# MCU_32.net
KiCad netlist of a schematic drawn in Altium Designer
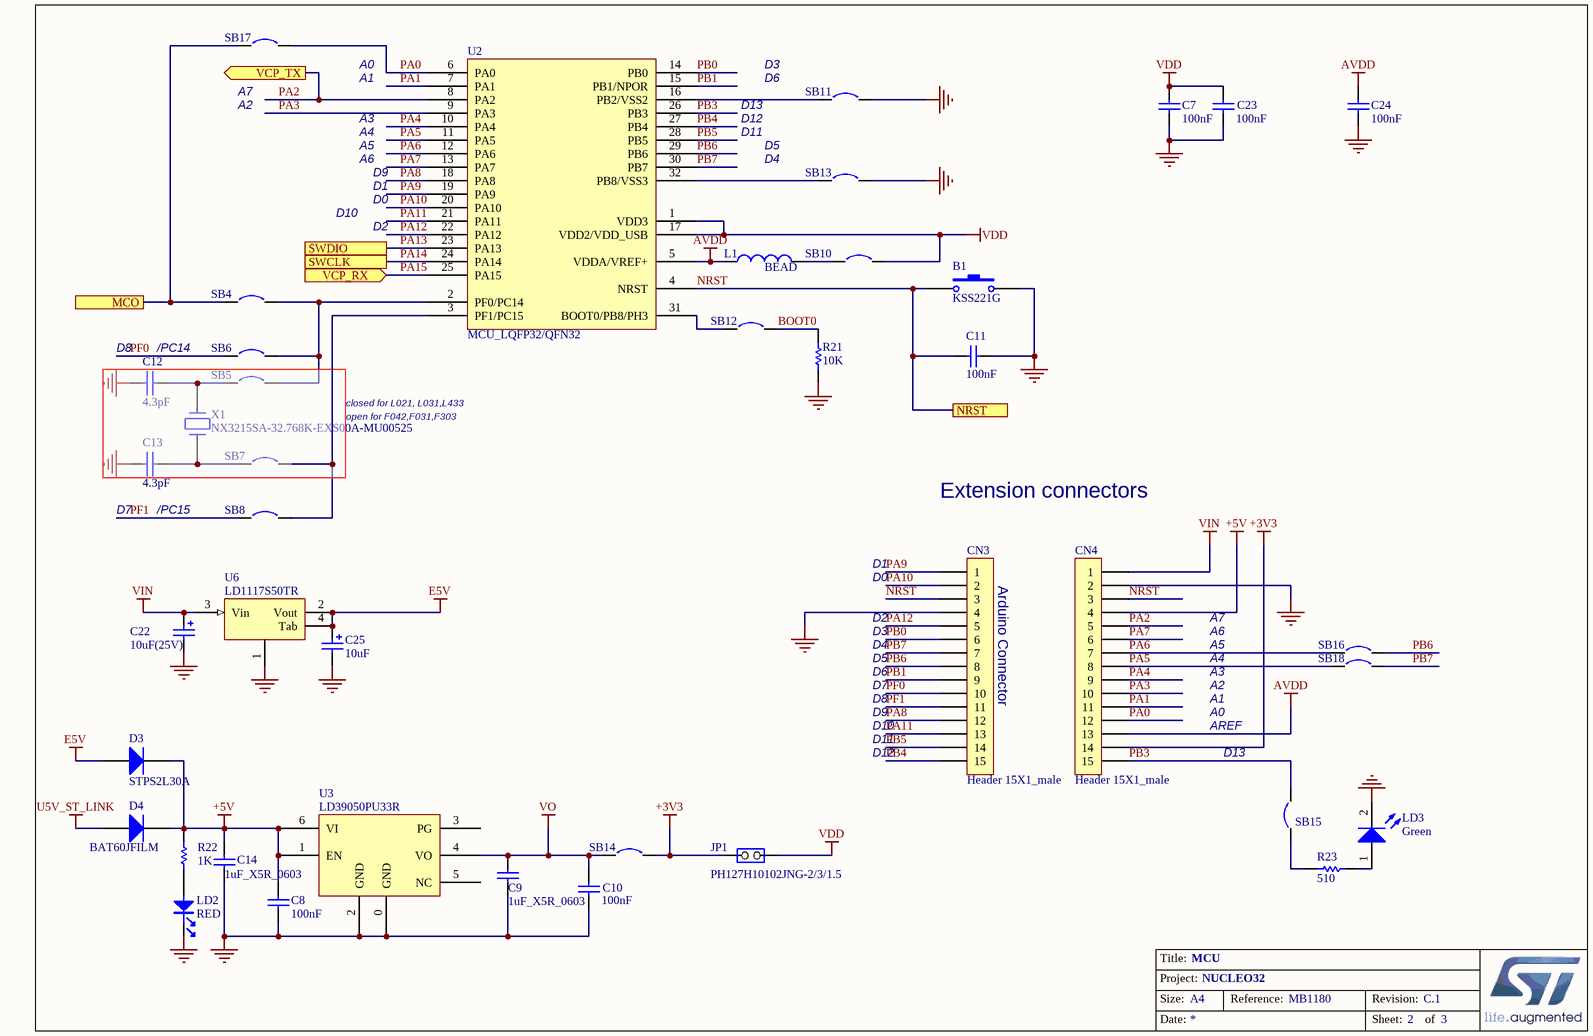
[diagram p0: MCU_32.SchDoc]

(export (version "E")
  (design (tool "Eeschema 10.0.6"))
  (components
    (comp (ref "B1")
      (value "KSS221G")
      (footprint "SW2_5R6_5R5x3R1")
      (description "Switch")
      (fields (field (name "PUBLISHER") "Altium Limited"))
      (libsource (lib "Miscellaneous Devices") (part "SW-PB"))
    )
    (comp (ref "C7")
      (value "100nF")
      (footprint "0603C")
      (description "Capacitor")
      (fields (field (name "PUBLISHER") "Altium Limited"))
      (libsource (lib "Miscellaneous Devices") (part "Cap"))
    )
    (comp (ref "C8")
      (value "100nF")
      (footprint "0603C")
      (description "Capacitor 0402 / 0603 / 0805")
      (libsource (lib "MCD_TOOLS") (part "Capacitor_ST"))
    )
    (comp (ref "C9")
      (value "1uF_X5R_0603")
      (footprint "0603C")
      (description "0603  X5R 1µF")
      (fields (field (name "TOLERANCE") "10%"))
      (libsource (lib "MB963_1") (part "CAP SMD 0603  X5R 1µF 25V 10%"))
    )
    (comp (ref "C10")
      (value "100nF")
      (footprint "0603C")
      (description "Capacitor 0402 / 0603 / 0805")
      (libsource (lib "MCD_TOOLS") (part "Capacitor_ST"))
    )
    (comp (ref "C11")
      (value "100nF")
      (footprint "0603C")
      (description "Capacitor")
      (fields (field (name "PUBLISHER") "Altium Limited"))
      (libsource (lib "Miscellaneous Devices") (part "CAP"))
    )
    (comp (ref "C12")
      (value "4.3pF")
      (footprint "0603C")
      (description "Capacitor")
      (libsource (lib "*") (part "CAP"))
    )
    (comp (ref "C13")
      (value "4.3pF")
      (footprint "0603C")
      (description "Capacitor")
      (libsource (lib "*") (part "CAP"))
    )
    (comp (ref "C14")
      (value "1uF_X5R_0603")
      (footprint "0603C")
      (description "0603  X5R 1µF")
      (fields (field (name "TOLERANCE") "10%"))
      (libsource (lib "MB963_1") (part "CAP SMD 0603  X5R 1µF 25V 10%"))
    )
    (comp (ref "C22")
      (value "10uF(25V)")
      (footprint "TAN_B")
      (description "Polarized Capacitor (Radial)")
      (fields (field (name "PUBLISHER") "Altium Limited"))
      (libsource (lib "Miscellaneous Devices") (part "Cap Pol1"))
    )
    (comp (ref "C23")
      (value "100nF")
      (footprint "0603C")
      (description "Capacitor")
      (fields (field (name "PUBLISHER") "Altium Limited"))
      (libsource (lib "Miscellaneous Devices") (part "Cap"))
    )
    (comp (ref "C24")
      (value "100nF")
      (footprint "0603C")
      (description "Capacitor")
      (fields (field (name "PUBLISHER") "Altium Limited"))
      (libsource (lib "Miscellaneous Devices") (part "Cap"))
    )
    (comp (ref "C25")
      (value "10uF")
      (footprint "TAN_A")
      (description "Polarized Capacitor (Radial)")
      (fields (field (name "PUBLISHER") "Altium Limited"))
      (libsource (lib "Miscellaneous Devices") (part "Cap Pol1"))
    )
    (comp (ref "CN3")
      (value "Header 15X1_male")
      (footprint "HDR_1x15_2R54_V_F")
      (description "Header, 10-Pin, Single row,female")
      (fields (field (name "PUBLISHER") "Altium Limited"))
      (libsource (lib "") (part "Header 15X1_Female_1_1"))
    )
    (comp (ref "CN4")
      (value "Header 15X1_male")
      (footprint "HDR_1x15_2R54_V_F")
      (description "Header, 10-Pin, Single row,female")
      (fields (field (name "PUBLISHER") "Altium Limited"))
      (libsource (lib "MB1180") (part "Header 15X1_Female_1"))
    )
    (comp (ref "D3") (value "STPS2L30A") (footprint "SMA") (libsource (lib "Nucleo_64") (part "STPS2L30A")))
    (comp (ref "D4")
      (value "BAT60JFILM")
      (footprint "SOD-323")
      (libsource (lib "MCD_TOOLS") (part "BAT60JFILM"))
    )
    (comp (ref "JP1")
      (value "PH127H10102JNG-2/3/1.5")
      (footprint "HDR_1x2_1R27_R_M")
      (libsource (lib "*") (part "JP2"))
    )
    (comp (ref "L1")
      (value "BEAD")
      (footprint "0603L")
      (description "Inductor")
      (fields (field (name "PUBLISHER") "Altium Limited"))
      (libsource (lib "Miscellaneous Devices") (part "Inductor"))
    )
    (comp (ref "LD2") (value "RED") (footprint "0603D_R") (libsource (lib "MB963_1") (part "PHOTO")))
    (comp (ref "LD3")
      (value "Green")
      (footprint "0603D_G")
      (description "Typical RED, GREEN, YELLOW, AMBER GaAs LED")
      (fields (field (name "PUBLISHER") "Altium Limited"))
      (libsource (lib "Miscellaneous Devices") (part "LED2"))
    )
    (comp (ref "R21")
      (value "10K")
      (footprint "0603R")
      (description "Resistor")
      (fields (field (name "PUBLISHER") "Altium Limited"))
      (libsource (lib "Miscellaneous Devices") (part "res1"))
    )
    (comp (ref "R22")
      (value "1K")
      (footprint "0603R")
      (description "Resistor 0402 / 0603 / 0805")
      (libsource (lib "MCD_TOOLS") (part "Resistor_ST"))
    )
    (comp (ref "R23")
      (value "510")
      (footprint "0603R")
      (description "Resistor")
      (fields (field (name "PUBLISHER") "Altium Limited"))
      (libsource (lib "Miscellaneous Devices") (part "Res1"))
    )
    (comp (ref "SB4")
      (value "Circuit Breaker (open)")
      (footprint "SB_0603")
      (description "Circuit Breaker")
      (fields (field (name "PUBLISHER") "Altium Limited"))
      (libsource (lib "MCD_TOOLS") (part "Circuit Breaker"))
    )
    (comp (ref "SB5")
      (value "Circuit Breaker")
      (footprint "SB_0603")
      (fields (field (name "PUBLISHER") "Altium Limited"))
      (libsource (lib "MCD_TOOLS") (part "Circuit Breaker"))
    )
    (comp (ref "SB6")
      (value "Circuit Breaker")
      (footprint "SB_0603")
      (fields (field (name "PUBLISHER") "Altium Limited"))
      (libsource (lib "MCD_TOOLS") (part "Circuit Breaker"))
    )
    (comp (ref "SB7")
      (value "Circuit Breaker")
      (footprint "SB_0603")
      (fields (field (name "PUBLISHER") "Altium Limited"))
      (libsource (lib "MCD_TOOLS") (part "Circuit Breaker"))
    )
    (comp (ref "SB8")
      (value "Circuit Breaker")
      (footprint "SB_0603")
      (fields (field (name "PUBLISHER") "Altium Limited"))
      (libsource (lib "MCD_TOOLS") (part "Circuit Breaker"))
    )
    (comp (ref "SB10")
      (value "Circuit Breaker (close)")
      (footprint "SB_0603")
      (description "Circuit Breaker")
      (fields (field (name "PUBLISHER") "Altium Limited"))
      (libsource (lib "MCD_TOOLS") (part "Circuit Breaker"))
    )
    (comp (ref "SB11")
      (value "Circuit Breaker (close)")
      (footprint "SB_0603")
      (description "Circuit Breaker")
      (fields (field (name "PUBLISHER") "Altium Limited"))
      (libsource (lib "MCD_TOOLS") (part "Circuit Breaker"))
    )
    (comp (ref "SB12")
      (value "Circuit Breaker (close)")
      (footprint "SB_0603")
      (description "Circuit Breaker")
      (fields (field (name "PUBLISHER") "Altium Limited"))
      (libsource (lib "MCD_TOOLS") (part "Circuit Breaker"))
    )
    (comp (ref "SB13")
      (value "Circuit Breaker (close)")
      (footprint "SB_0603")
      (description "Circuit Breaker")
      (fields (field (name "PUBLISHER") "Altium Limited"))
      (libsource (lib "MCD_TOOLS") (part "Circuit Breaker"))
    )
    (comp (ref "SB14")
      (value "Circuit Breaker (close)")
      (footprint "SB_0603")
      (description "Circuit Breaker")
      (fields (field (name "PUBLISHER") "Altium Limited"))
      (libsource (lib "MCD_TOOLS") (part "Circuit Breaker"))
    )
    (comp (ref "SB15")
      (value "Circuit Breaker (close)")
      (footprint "SB_0603")
      (description "Circuit Breaker")
      (fields (field (name "PUBLISHER") "Altium Limited"))
      (libsource (lib "MCD_TOOLS") (part "Circuit Breaker"))
    )
    (comp (ref "SB16")
      (value "Circuit Breaker (close)")
      (footprint "SB_0603")
      (description "Circuit Breaker")
      (fields (field (name "PUBLISHER") "Altium Limited"))
      (libsource (lib "MCD_TOOLS") (part "Circuit Breaker"))
    )
    (comp (ref "SB17")
      (value "Circuit Breaker (open)")
      (footprint "SB_0603")
      (description "Circuit Breaker")
      (fields (field (name "PUBLISHER") "Altium Limited"))
      (libsource (lib "MCD_TOOLS") (part "Circuit Breaker"))
    )
    (comp (ref "SB18")
      (value "Circuit Breaker (close)")
      (footprint "SB_0603")
      (description "Circuit Breaker")
      (fields (field (name "PUBLISHER") "Altium Limited"))
      (libsource (lib "MCD_TOOLS") (part "Circuit Breaker"))
    )
    (comp (ref "U2")
      (value "MCU_LQFP32/QFN32")
      (footprint "LQFP32_0R5_7x7")
      (libsource (lib "MB1180") (part "MCU_LQFP32"))
    )
    (comp (ref "U3")
      (value "LD39050PU33R")
      (footprint "DFN6_0R95_3x3_TP")
      (libsource (lib "MB1180") (part "LD39050P"))
    )
    (comp (ref "U6") (value "LD1117S50TR") (footprint "SOT-223") (libsource (lib "MB1180") (part "LD1117")))
    (comp (ref "X1")
      (value "NX3215SA-32.768K-EXS00A-MU00525")
      (footprint "XTAL_2SM_3R2X1R5")
      (description "Crystal")
      (libsource (lib "MB1167") (part "CRYSTAL_32K"))
    )
  )
  (nets
    (net (code "1") (name "+3V3") (class "Default")
      (node (ref "CN4") (pin "14") (pinfunction "14_14") (pintype "passive"))
      (node (ref "JP1") (pin "1") (pinfunction "COMMON_1") (pintype "passive"))
      (node (ref "SB14") (pin "2") (pinfunction "2_2") (pintype "passive"))
    )
    (net (code "2") (name "+5V") (class "Default")
      (node (ref "C14") (pin "1") (pinfunction "1_1") (pintype "passive"))
      (node (ref "C8") (pin "2") (pinfunction "2_2") (pintype "passive"))
      (node (ref "CN4") (pin "4") (pinfunction "4_4") (pintype "passive"))
      (node (ref "D3") (pin "2") (pinfunction "K_2") (pintype "passive"))
      (node (ref "D4") (pin "2") (pinfunction "K_2") (pintype "passive"))
      (node (ref "R22") (pin "2") (pinfunction "2_2") (pintype "passive"))
      (node (ref "U3") (pin "1") (pinfunction "EN_1") (pintype "passive"))
      (node (ref "U3") (pin "6") (pinfunction "VI_6") (pintype "passive"))
    )
    (net (code "3") (name "/BOOT0") (class "Default")
      (node (ref "R21") (pin "1") (pinfunction "1_1") (pintype "passive"))
      (node (ref "SB12") (pin "2") (pinfunction "2_2") (pintype "passive"))
    )
    (net (code "4") (name "/MCO") (class "Default")
      (node (ref "SB17") (pin "1") (pinfunction "1_1") (pintype "passive"))
      (node (ref "SB4") (pin "1") (pinfunction "1_1") (pintype "passive"))
    )
    (net (code "5") (name "/NRST") (class "Default")
      (node (ref "B1") (pin "1") (pinfunction "1_1") (pintype "passive"))
      (node (ref "C11") (pin "2") (pinfunction "2_2") (pintype "passive"))
      (node (ref "CN3") (pin "3") (pinfunction "3_3") (pintype "passive"))
      (node (ref "CN4") (pin "3") (pinfunction "3_3") (pintype "passive"))
      (node (ref "U2") (pin "4") (pinfunction "NRST_4") (pintype "passive"))
    )
    (net (code "6") (name "/PA0") (class "Default")
      (node (ref "CN4") (pin "12") (pinfunction "12_12") (pintype "passive"))
      (node (ref "SB17") (pin "2") (pinfunction "2_2") (pintype "passive"))
      (node (ref "U2") (pin "6") (pinfunction "PA0_6") (pintype "passive"))
    )
    (net (code "7") (name "/PA1") (class "Default")
      (node (ref "CN4") (pin "11") (pinfunction "11_11") (pintype "passive"))
      (node (ref "U2") (pin "7") (pinfunction "PA1_7") (pintype "passive"))
    )
    (net (code "8") (name "/PA2") (class "Default")
      (node (ref "CN4") (pin "5") (pinfunction "5_5") (pintype "passive"))
      (node (ref "U2") (pin "8") (pinfunction "PA2_8") (pintype "passive"))
    )
    (net (code "9") (name "/PA3") (class "Default")
      (node (ref "CN4") (pin "10") (pinfunction "10_10") (pintype "passive"))
      (node (ref "U2") (pin "9") (pinfunction "PA3_9") (pintype "passive"))
    )
    (net (code "10") (name "/PA4") (class "Default")
      (node (ref "CN4") (pin "9") (pinfunction "9_9") (pintype "passive"))
      (node (ref "U2") (pin "10") (pinfunction "PA4_10") (pintype "passive"))
    )
    (net (code "11") (name "/PA5") (class "Default")
      (node (ref "CN4") (pin "8") (pinfunction "8_8") (pintype "passive"))
      (node (ref "SB18") (pin "1") (pinfunction "1_1") (pintype "passive"))
      (node (ref "U2") (pin "11") (pinfunction "PA5_11") (pintype "passive"))
    )
    (net (code "12") (name "/PA6") (class "Default")
      (node (ref "CN4") (pin "7") (pinfunction "7_7") (pintype "passive"))
      (node (ref "SB16") (pin "1") (pinfunction "1_1") (pintype "passive"))
      (node (ref "U2") (pin "12") (pinfunction "PA6_12") (pintype "passive"))
    )
    (net (code "13") (name "/PA7") (class "Default")
      (node (ref "CN4") (pin "6") (pinfunction "6_6") (pintype "passive"))
      (node (ref "U2") (pin "13") (pinfunction "PA7_13") (pintype "passive"))
    )
    (net (code "14") (name "/PA8") (class "Default")
      (node (ref "CN3") (pin "12") (pinfunction "12_12") (pintype "passive"))
      (node (ref "U2") (pin "18") (pinfunction "PA8_18") (pintype "passive"))
    )
    (net (code "15") (name "/PA9") (class "Default")
      (node (ref "CN3") (pin "1") (pinfunction "1_1") (pintype "passive"))
      (node (ref "U2") (pin "19") (pinfunction "PA9_19") (pintype "passive"))
    )
    (net (code "16") (name "/PA10") (class "Default")
      (node (ref "CN3") (pin "2") (pinfunction "2_2") (pintype "passive"))
      (node (ref "U2") (pin "20") (pinfunction "PA10_20") (pintype "passive"))
    )
    (net (code "17") (name "/PA11") (class "Default")
      (node (ref "CN3") (pin "13") (pinfunction "13_13") (pintype "passive"))
      (node (ref "U2") (pin "21") (pinfunction "PA11_21") (pintype "passive"))
    )
    (net (code "18") (name "/PA12") (class "Default")
      (node (ref "CN3") (pin "5") (pinfunction "5_5") (pintype "passive"))
      (node (ref "U2") (pin "22") (pinfunction "PA12_22") (pintype "passive"))
    )
    (net (code "19") (name "/PA13") (class "Default")
      (node (ref "U2") (pin "23") (pinfunction "PA13_23") (pintype "passive"))
    )
    (net (code "20") (name "/PA14") (class "Default")
      (node (ref "U2") (pin "24") (pinfunction "PA14_24") (pintype "passive"))
    )
    (net (code "21") (name "/PA15") (class "Default")
      (node (ref "U2") (pin "25") (pinfunction "PA15_25") (pintype "passive"))
    )
    (net (code "22") (name "/PB0") (class "Default")
      (node (ref "CN3") (pin "6") (pinfunction "6_6") (pintype "passive"))
      (node (ref "U2") (pin "14") (pinfunction "PB0_14") (pintype "passive"))
    )
    (net (code "23") (name "/PB1") (class "Default")
      (node (ref "CN3") (pin "9") (pinfunction "9_9") (pintype "passive"))
      (node (ref "U2") (pin "15") (pinfunction "PB1/NPOR_15") (pintype "passive"))
    )
    (net (code "24") (name "/PB3") (class "Default")
      (node (ref "CN4") (pin "15") (pinfunction "15_15") (pintype "passive"))
      (node (ref "SB15") (pin "2") (pinfunction "2_2") (pintype "passive"))
      (node (ref "U2") (pin "26") (pinfunction "PB3_26") (pintype "passive"))
    )
    (net (code "25") (name "/PB4") (class "Default")
      (node (ref "CN3") (pin "15") (pinfunction "15_15") (pintype "passive"))
      (node (ref "U2") (pin "27") (pinfunction "PB4_27") (pintype "passive"))
    )
    (net (code "26") (name "/PB5") (class "Default")
      (node (ref "CN3") (pin "14") (pinfunction "14_14") (pintype "passive"))
      (node (ref "U2") (pin "28") (pinfunction "PB5_28") (pintype "passive"))
    )
    (net (code "27") (name "/PB6") (class "Default")
      (node (ref "CN3") (pin "8") (pinfunction "8_8") (pintype "passive"))
      (node (ref "SB16") (pin "2") (pinfunction "2_2") (pintype "passive"))
      (node (ref "U2") (pin "29") (pinfunction "PB6_29") (pintype "passive"))
    )
    (net (code "28") (name "/PB7") (class "Default")
      (node (ref "CN3") (pin "7") (pinfunction "7_7") (pintype "passive"))
      (node (ref "SB18") (pin "2") (pinfunction "2_2") (pintype "passive"))
      (node (ref "U2") (pin "30") (pinfunction "PB7_30") (pintype "passive"))
    )
    (net (code "29") (name "/PF0") (class "Default")
      (node (ref "CN3") (pin "10") (pinfunction "10_10") (pintype "passive"))
      (node (ref "SB6") (pin "1") (pinfunction "1_1") (pintype "passive"))
    )
    (net (code "30") (name "/PF1") (class "Default")
      (node (ref "CN3") (pin "11") (pinfunction "11_11") (pintype "passive"))
      (node (ref "SB8") (pin "1") (pinfunction "1_1") (pintype "passive"))
    )
    (net (code "31") (name "AVDD") (class "Default")
      (node (ref "C24") (pin "1") (pinfunction "1_1") (pintype "passive"))
      (node (ref "CN4") (pin "13") (pinfunction "13_13") (pintype "passive"))
      (node (ref "L1") (pin "1") (pinfunction "1_1") (pintype "passive"))
      (node (ref "U2") (pin "5") (pinfunction "VDDA/VREF+_5") (pintype "passive"))
    )
    (net (code "32") (name "E5V") (class "Default")
      (node (ref "C25") (pin "1") (pinfunction "1_1") (pintype "passive"))
      (node (ref "D3") (pin "1") (pinfunction "A_1") (pintype "passive"))
      (node (ref "U6") (pin "2") (pinfunction "Vout_2") (pintype "power_in"))
      (node (ref "U6") (pin "4") (pinfunction "Tab_4") (pintype "power_in"))
    )
    (net (code "33") (name "GND") (class "Default")
      (node (ref "B1") (pin "2") (pinfunction "2_2") (pintype "passive"))
      (node (ref "C10") (pin "1") (pinfunction "1_1") (pintype "passive"))
      (node (ref "C11") (pin "1") (pinfunction "1_1") (pintype "passive"))
      (node (ref "C12") (pin "2") (pinfunction "2_2") (pintype "passive"))
      (node (ref "C13") (pin "2") (pinfunction "2_2") (pintype "passive"))
      (node (ref "C14") (pin "2") (pinfunction "2_2") (pintype "passive"))
      (node (ref "C22") (pin "2") (pinfunction "2_2") (pintype "passive"))
      (node (ref "C23") (pin "2") (pinfunction "2_2") (pintype "passive"))
      (node (ref "C24") (pin "2") (pinfunction "2_2") (pintype "passive"))
      (node (ref "C25") (pin "2") (pinfunction "2_2") (pintype "passive"))
      (node (ref "C7") (pin "2") (pinfunction "2_2") (pintype "passive"))
      (node (ref "C8") (pin "1") (pinfunction "1_1") (pintype "passive"))
      (node (ref "C9") (pin "2") (pinfunction "2_2") (pintype "passive"))
      (node (ref "CN3") (pin "4") (pinfunction "4_4") (pintype "passive"))
      (node (ref "CN4") (pin "2") (pinfunction "2_2") (pintype "passive"))
      (node (ref "LD2") (pin "2") (pintype "passive"))
      (node (ref "LD3") (pin "2") (pinfunction "K_2") (pintype "passive"))
      (node (ref "R21") (pin "2") (pinfunction "2_2") (pintype "passive"))
      (node (ref "SB11") (pin "2") (pinfunction "2_2") (pintype "passive"))
      (node (ref "SB13") (pin "2") (pinfunction "2_2") (pintype "passive"))
      (node (ref "U3") (pin "0") (pinfunction "GND_0") (pintype "passive"))
      (node (ref "U3") (pin "2") (pinfunction "GND_2") (pintype "passive"))
      (node (ref "U6") (pin "1") (pintype "passive"))
    )
    (net (code "34") (name "Net-(C12-Pad1)") (class "Default")
      (node (ref "C12") (pin "1") (pinfunction "1_1") (pintype "passive"))
      (node (ref "SB5") (pin "1") (pinfunction "1_1") (pintype "passive"))
      (node (ref "X1") (pin "1") (pinfunction "1_1") (pintype "passive"))
    )
    (net (code "35") (name "Net-(C13-Pad1)") (class "Default")
      (node (ref "C13") (pin "1") (pinfunction "1_1") (pintype "passive"))
      (node (ref "SB7") (pin "1") (pinfunction "1_1") (pintype "passive"))
      (node (ref "X1") (pin "2") (pinfunction "2_2") (pintype "passive"))
    )
    (net (code "36") (name "Net-(L1-Pad2)") (class "Default")
      (node (ref "L1") (pin "2") (pinfunction "2_2") (pintype "passive"))
      (node (ref "SB10") (pin "1") (pinfunction "1_1") (pintype "passive"))
    )
    (net (code "37") (name "Net-(LD2-Pad1)") (class "Default")
      (node (ref "LD2") (pin "1") (pintype "passive"))
      (node (ref "R22") (pin "1") (pinfunction "1_1") (pintype "passive"))
    )
    (net (code "38") (name "Net-(LD3-A)") (class "Default")
      (node (ref "LD3") (pin "1") (pinfunction "A_1") (pintype "passive"))
      (node (ref "R23") (pin "1") (pinfunction "1_1") (pintype "passive"))
    )
    (net (code "39") (name "Net-(R23-Pad2)") (class "Default")
      (node (ref "R23") (pin "2") (pinfunction "2_2") (pintype "passive"))
      (node (ref "SB15") (pin "1") (pinfunction "1_1") (pintype "passive"))
    )
    (net (code "40") (name "Net-(U2-BOOT0{slash}PB8{slash}PH3)") (class "Default")
      (node (ref "SB12") (pin "1") (pinfunction "1_1") (pintype "passive"))
      (node (ref "U2") (pin "31") (pinfunction "BOOT0/PB8/PH3_31") (pintype "passive"))
    )
    (net (code "41") (name "Net-(U2-PB2{slash}VSS2)") (class "Default")
      (node (ref "SB11") (pin "1") (pinfunction "1_1") (pintype "passive"))
      (node (ref "U2") (pin "16") (pinfunction "PB2/VSS2_16") (pintype "passive"))
    )
    (net (code "42") (name "Net-(U2-PB8{slash}VSS3)") (class "Default")
      (node (ref "SB13") (pin "1") (pinfunction "1_1") (pintype "passive"))
      (node (ref "U2") (pin "32") (pinfunction "PB8/VSS3_32") (pintype "passive"))
    )
    (net (code "43") (name "Net-(U2-PF0{slash}PC14)") (class "Default")
      (node (ref "SB4") (pin "2") (pinfunction "2_2") (pintype "passive"))
      (node (ref "SB5") (pin "2") (pinfunction "2_2") (pintype "passive"))
      (node (ref "SB6") (pin "2") (pinfunction "2_2") (pintype "passive"))
      (node (ref "U2") (pin "2") (pinfunction "PF0/PC14_2") (pintype "passive"))
    )
    (net (code "44") (name "Net-(U2-PF1{slash}PC15)") (class "Default")
      (node (ref "SB7") (pin "2") (pinfunction "2_2") (pintype "passive"))
      (node (ref "SB8") (pin "2") (pinfunction "2_2") (pintype "passive"))
      (node (ref "U2") (pin "3") (pinfunction "PF1/PC15_3") (pintype "passive"))
    )
    (net (code "45") (name "U5V_ST_LINK") (class "Default")
      (node (ref "D4") (pin "1") (pinfunction "A_1") (pintype "passive"))
    )
    (net (code "46") (name "VDD") (class "Default")
      (node (ref "C23") (pin "1") (pinfunction "1_1") (pintype "passive"))
      (node (ref "C7") (pin "1") (pinfunction "1_1") (pintype "passive"))
      (node (ref "JP1") (pin "2") (pinfunction "NO_2") (pintype "passive"))
      (node (ref "SB10") (pin "2") (pinfunction "2_2") (pintype "passive"))
      (node (ref "U2") (pin "1") (pinfunction "VDD3_1") (pintype "passive"))
      (node (ref "U2") (pin "17") (pinfunction "VDD2/VDD_USB_17") (pintype "passive"))
    )
    (net (code "47") (name "VIN") (class "Default")
      (node (ref "C22") (pin "1") (pinfunction "1_1") (pintype "passive"))
      (node (ref "CN4") (pin "1") (pinfunction "1_1") (pintype "passive"))
      (node (ref "U6") (pin "3") (pinfunction "Vin_3") (pintype "input"))
    )
    (net (code "48") (name "VO") (class "Default")
      (node (ref "C10") (pin "2") (pinfunction "2_2") (pintype "passive"))
      (node (ref "C9") (pin "1") (pinfunction "1_1") (pintype "passive"))
      (node (ref "SB14") (pin "1") (pinfunction "1_1") (pintype "passive"))
      (node (ref "U3") (pin "4") (pinfunction "VO_4") (pintype "passive"))
    )
    (net (code "49") (name "unconnected-(U3-NC-Pad5)") (class "Default")
      (node (ref "U3") (pin "5") (pinfunction "NC_5") (pintype "passive"))
    )
    (net (code "50") (name "unconnected-(U3-PG-Pad3)") (class "Default")
      (node (ref "U3") (pin "3") (pinfunction "PG_3") (pintype "passive"))
    )
  )
)
